# PracticePCB.net
KiCad netlist of a schematic drawn in Altium Designer
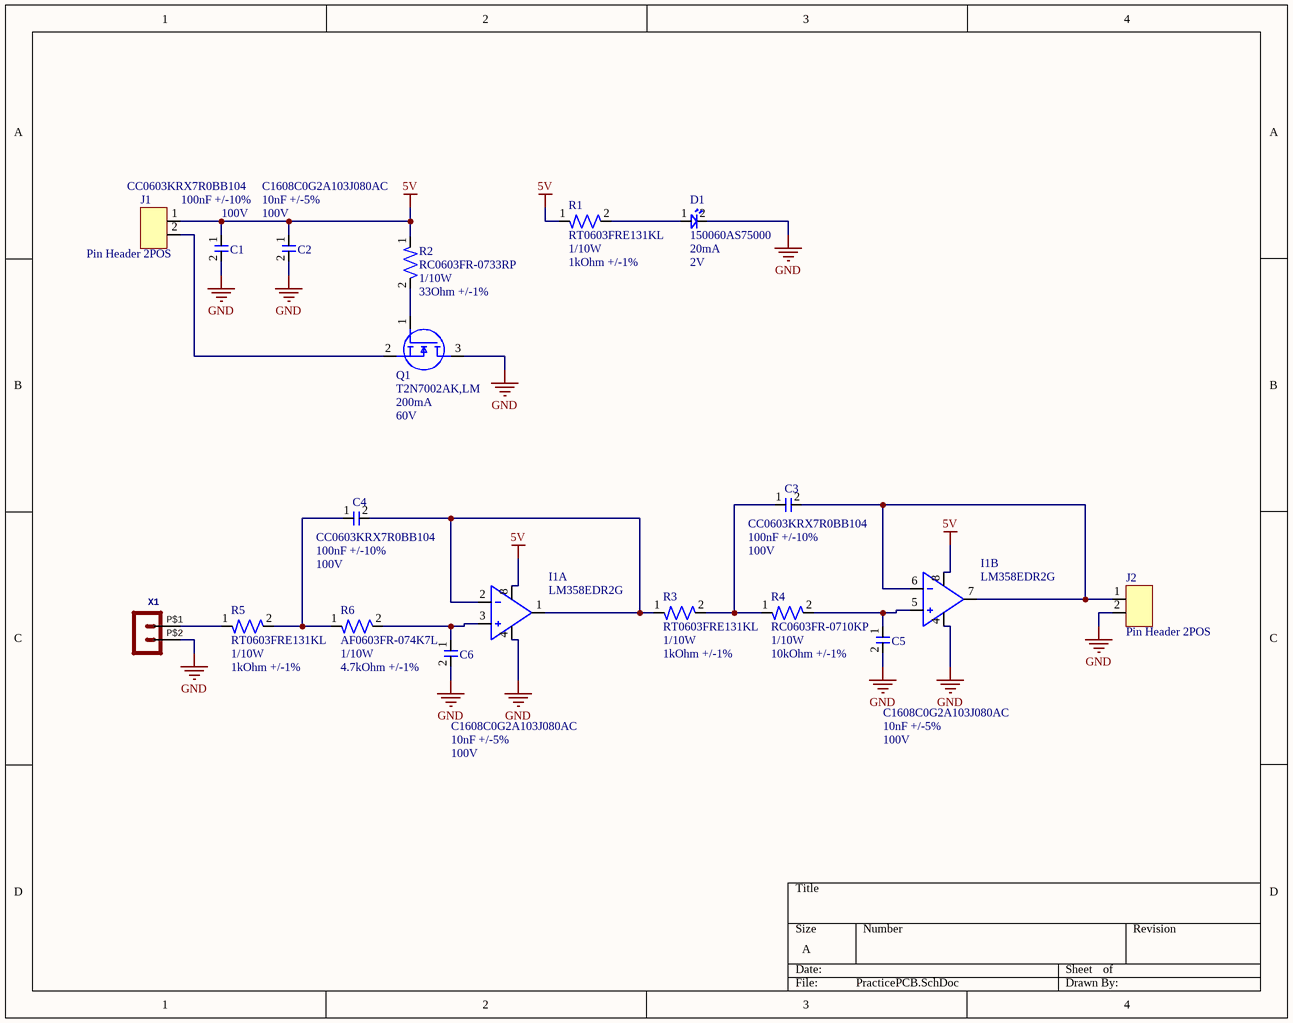
[diagram p0: PracticePCB.SchDoc]

(export (version "E")
  (design (tool "Eeschema 10.0.6"))
  (components
    (comp (ref "C1")
      (value "CC0603KRX7R0BB104")
      (footprint "CAP-0603")
      (description "CAP CER 0.1UF 100V X7R 0603")
      (fields
        (field (name "MANUFACTURER") "YAGEO")
        (field (name "CAPACITANCE") "100nF +/-10%")
        (field (name "VOLTAGE RATING") "100V")
      )
      (libsource (lib "MasterLib") (part "CAP-100N-0001"))
    )
    (comp (ref "C2")
      (value "C1608C0G2A103J080AC")
      (footprint "CAP-0603")
      (description "CAP CER 10000PF 100V C0G 0603")
      (fields
        (field (name "MANUFACTURER") "TDK Corporation")
        (field (name "CAPACITANCE") "10nF +/-5%")
        (field (name "VOLTAGE RATING") "100V")
      )
      (libsource (lib "MasterLib") (part "CAP-10N-0002"))
    )
    (comp (ref "C3")
      (value "CC0603KRX7R0BB104")
      (footprint "CAP-0603")
      (description "CAP CER 0.1UF 100V X7R 0603")
      (fields
        (field (name "MANUFACTURER") "YAGEO")
        (field (name "CAPACITANCE") "100nF +/-10%")
        (field (name "VOLTAGE RATING") "100V")
      )
      (libsource (lib "MasterLib") (part "CAP-100N-0001"))
    )
    (comp (ref "C4")
      (value "CC0603KRX7R0BB104")
      (footprint "CAP-0603")
      (description "CAP CER 0.1UF 100V X7R 0603")
      (fields
        (field (name "MANUFACTURER") "YAGEO")
        (field (name "CAPACITANCE") "100nF +/-10%")
        (field (name "VOLTAGE RATING") "100V")
      )
      (libsource (lib "MasterLib") (part "CAP-100N-0001"))
    )
    (comp (ref "C5")
      (value "C1608C0G2A103J080AC")
      (footprint "CAP-0603")
      (description "CAP CER 10000PF 100V C0G 0603")
      (fields
        (field (name "MANUFACTURER") "TDK Corporation")
        (field (name "CAPACITANCE") "10nF +/-5%")
        (field (name "VOLTAGE RATING") "100V")
      )
      (libsource (lib "MasterLib") (part "CAP-10N-0002"))
    )
    (comp (ref "C6")
      (value "C1608C0G2A103J080AC")
      (footprint "CAP-0603")
      (description "CAP CER 10000PF 100V C0G 0603")
      (fields
        (field (name "MANUFACTURER") "TDK Corporation")
        (field (name "CAPACITANCE") "10nF +/-5%")
        (field (name "VOLTAGE RATING") "100V")
      )
      (libsource (lib "MasterLib") (part "CAP-10N-0002"))
    )
    (comp (ref "D1")
      (value "150060AS75000")
      (footprint "LED-0603")
      (description "CAP CER 0.1UF 100V X7R 0603")
      (fields
        (field (name "MANUFACTURER") "Wurth Electronik")
        (field (name "CURRENT RATING") "20mA")
        (field (name "VF") "2V")
      )
      (libsource (lib "MasterLib") (part "LED_Amber_0001"))
    )
    (comp (ref "I1")
      (value "LM358EDR2G")
      (footprint "IC-OPAMP-0001")
      (description "IC OPAMP GP 2 CIRCUIT 8SOIC")
      (fields (field (name "MANUFACTURER") "onsemi"))
      (libsource (lib "MasterLib") (part "IC-OPAMP-0001"))
    )
    (comp (ref "J1")
      (value "Pin Header 2POS")
      (footprint "CON-2POS-0001")
      (libsource (lib "") (part "CON-2POS-0001_1"))
    )
    (comp (ref "J2")
      (value "Pin Header 2POS")
      (footprint "CON-2POS-0001")
      (libsource (lib "MasterLib") (part "CON-2POS-0001"))
    )
    (comp (ref "Q1")
      (value "T2N7002AK,LM")
      (footprint "NMOS-SOT23-3")
      (description "MOSFET N-CH 60V 200MA SOT23")
      (fields
        (field (name "MANUFACTURER") "Toshiba")
        (field (name "ID-CONTINUOUS") "200mA")
        (field (name "VDS-MAX") "60V")
      )
      (libsource (lib "MasterLib") (part "NMOS-200MA-0001"))
    )
    (comp (ref "R1")
      (value "RT0603FRE131KL")
      (footprint "RES-0603")
      (description "CHIP RESISTOR THIN FLIM HIGH PRE")
      (fields
        (field (name "MANUFACTURER") "YAGEO")
        (field (name "POWER RATING") "1/10W")
        (field (name "RESISTANCE") "1kOhm +/-1%")
      )
      (libsource (lib "MasterLib") (part "RES-1K-0002"))
    )
    (comp (ref "R2")
      (value "RC0603FR-0733RP")
      (footprint "RES-0603")
      (description "RES SMD 33 OHM 1% 1/10W 0603")
      (fields
        (field (name "MANUFACTURER") "YAGEO")
        (field (name "POWER RATING") "1/10W")
        (field (name "RESISTANCE") "33Ohm +/-1%")
      )
      (libsource (lib "MasterLib") (part "RES-33-0002"))
    )
    (comp (ref "R3")
      (value "RT0603FRE131KL")
      (footprint "RES-0603")
      (description "CHIP RESISTOR THIN FLIM HIGH PRE")
      (fields
        (field (name "MANUFACTURER") "YAGEO")
        (field (name "POWER RATING") "1/10W")
        (field (name "RESISTANCE") "1kOhm +/-1%")
      )
      (libsource (lib "MasterLib") (part "RES-1K-0002"))
    )
    (comp (ref "R4")
      (value "RC0603FR-0710KP")
      (footprint "RES-0603")
      (description "RES SMD 10K OHM 1% 1/10W 0603")
      (fields
        (field (name "MANUFACTURER") "YAGEO")
        (field (name "POWER RATING") "1/10W")
        (field (name "RESISTANCE") "10kOhm +/-1%")
      )
      (libsource (lib "MasterLib") (part "RES-10K-0002"))
    )
    (comp (ref "R5")
      (value "RT0603FRE131KL")
      (footprint "RES-0603")
      (description "CHIP RESISTOR THIN FLIM HIGH PRE")
      (fields
        (field (name "MANUFACTURER") "YAGEO")
        (field (name "POWER RATING") "1/10W")
        (field (name "RESISTANCE") "1kOhm +/-1%")
      )
      (libsource (lib "MasterLib") (part "RES-1K-0002"))
    )
    (comp (ref "R6")
      (value "AF0603FR-074K7L")
      (footprint "RES-0603")
      (description "RES SMD 4.7K OHM 1% 1/10W 0603")
      (fields
        (field (name "MANUFACTURER") "YAGEO")
        (field (name "POWER RATING") "1/10W")
        (field (name "RESISTANCE") "4.7kOhm +/-1%")
      )
      (libsource (lib "MasterLib") (part "RES-4.7K-0002"))
    )
    (comp (ref "X1")
      (value "Molex - Micro-Fit 3.0 Series connector,  3.00mm (0.118\") pitch header, 2 positions.")
      (footprint "44914-0201")
      (libsource (lib "Molex Microfit") (part "HEADER_POS2_?44914-0201"))
    )
  )
  (nets
    (net (code "1") (name "5V") (class "Default")
      (node (ref "C1") (pin "1") (pinfunction "1_1") (pintype "passive"))
      (node (ref "C2") (pin "1") (pinfunction "1_1") (pintype "passive"))
      (node (ref "I1") (pin "8") (pinfunction "8_8") (pintype "passive"))
      (node (ref "J1") (pin "1") (pintype "passive"))
      (node (ref "R1") (pin "1") (pinfunction "1_1") (pintype "passive"))
      (node (ref "R2") (pin "1") (pinfunction "1_1") (pintype "passive"))
    )
    (net (code "2") (name "GND") (class "Default")
      (node (ref "C1") (pin "2") (pinfunction "2_2") (pintype "passive"))
      (node (ref "C2") (pin "2") (pinfunction "2_2") (pintype "passive"))
      (node (ref "C5") (pin "2") (pinfunction "2_2") (pintype "passive"))
      (node (ref "C6") (pin "2") (pinfunction "2_2") (pintype "passive"))
      (node (ref "D1") (pin "2") (pinfunction "2_2") (pintype "passive"))
      (node (ref "I1") (pin "4") (pinfunction "4_4") (pintype "passive"))
      (node (ref "J2") (pin "2") (pinfunction "2_2") (pintype "passive"))
      (node (ref "Q1") (pin "3") (pinfunction "D_3") (pintype "passive"))
      (node (ref "X1") (pin "P$2") (pinfunction "2_P$2") (pintype "passive"))
    )
    (net (code "3") (name "Net-(C3-Pad1)") (class "Default")
      (node (ref "C3") (pin "1") (pinfunction "1_1") (pintype "passive"))
      (node (ref "R3") (pin "2") (pinfunction "2_2") (pintype "passive"))
      (node (ref "R4") (pin "1") (pinfunction "1_1") (pintype "passive"))
    )
    (net (code "4") (name "Net-(C3-Pad2)") (class "Default")
      (node (ref "C3") (pin "2") (pinfunction "2_2") (pintype "passive"))
      (node (ref "I1") (pin "6") (pinfunction "6_6") (pintype "passive"))
      (node (ref "I1") (pin "7") (pinfunction "7_7") (pintype "passive"))
      (node (ref "J2") (pin "1") (pintype "passive"))
    )
    (net (code "5") (name "Net-(C4-Pad1)") (class "Default")
      (node (ref "C4") (pin "1") (pinfunction "1_1") (pintype "passive"))
      (node (ref "R5") (pin "2") (pinfunction "2_2") (pintype "passive"))
      (node (ref "R6") (pin "1") (pinfunction "1_1") (pintype "passive"))
    )
    (net (code "6") (name "Net-(C4-Pad2)") (class "Default")
      (node (ref "C4") (pin "2") (pinfunction "2_2") (pintype "passive"))
      (node (ref "I1") (pin "1") (pinfunction "1_1") (pintype "passive"))
      (node (ref "I1") (pin "2") (pinfunction "2_2") (pintype "passive"))
      (node (ref "R3") (pin "1") (pinfunction "1_1") (pintype "passive"))
    )
    (net (code "7") (name "Net-(C5-Pad1)") (class "Default")
      (node (ref "C5") (pin "1") (pinfunction "1_1") (pintype "passive"))
      (node (ref "I1") (pin "5") (pinfunction "5_5") (pintype "passive"))
      (node (ref "R4") (pin "2") (pinfunction "2_2") (pintype "passive"))
    )
    (net (code "8") (name "Net-(C6-Pad1)") (class "Default")
      (node (ref "C6") (pin "1") (pinfunction "1_1") (pintype "passive"))
      (node (ref "I1") (pin "3") (pinfunction "3_3") (pintype "passive"))
      (node (ref "R6") (pin "2") (pinfunction "2_2") (pintype "passive"))
    )
    (net (code "9") (name "Net-(D1-Pad1)") (class "Default")
      (node (ref "D1") (pin "1") (pinfunction "1_1") (pintype "passive"))
      (node (ref "R1") (pin "2") (pinfunction "2_2") (pintype "passive"))
    )
    (net (code "10") (name "Net-(Q1-G)") (class "Default")
      (node (ref "Q1") (pin "1") (pinfunction "G_1") (pintype "passive"))
      (node (ref "R2") (pin "2") (pinfunction "2_2") (pintype "passive"))
    )
    (net (code "11") (name "Net-(Q1-S)") (class "Default")
      (node (ref "J1") (pin "2") (pinfunction "2_2") (pintype "passive"))
      (node (ref "Q1") (pin "2") (pinfunction "S_2") (pintype "passive"))
    )
    (net (code "12") (name "Net-(X1-1)") (class "Default")
      (node (ref "R5") (pin "1") (pinfunction "1_1") (pintype "passive"))
      (node (ref "X1") (pin "P$1") (pinfunction "1_P$1") (pintype "passive"))
    )
  )
)
